# Sheet1.net
KiCad netlist of a schematic drawn in Altium Designer
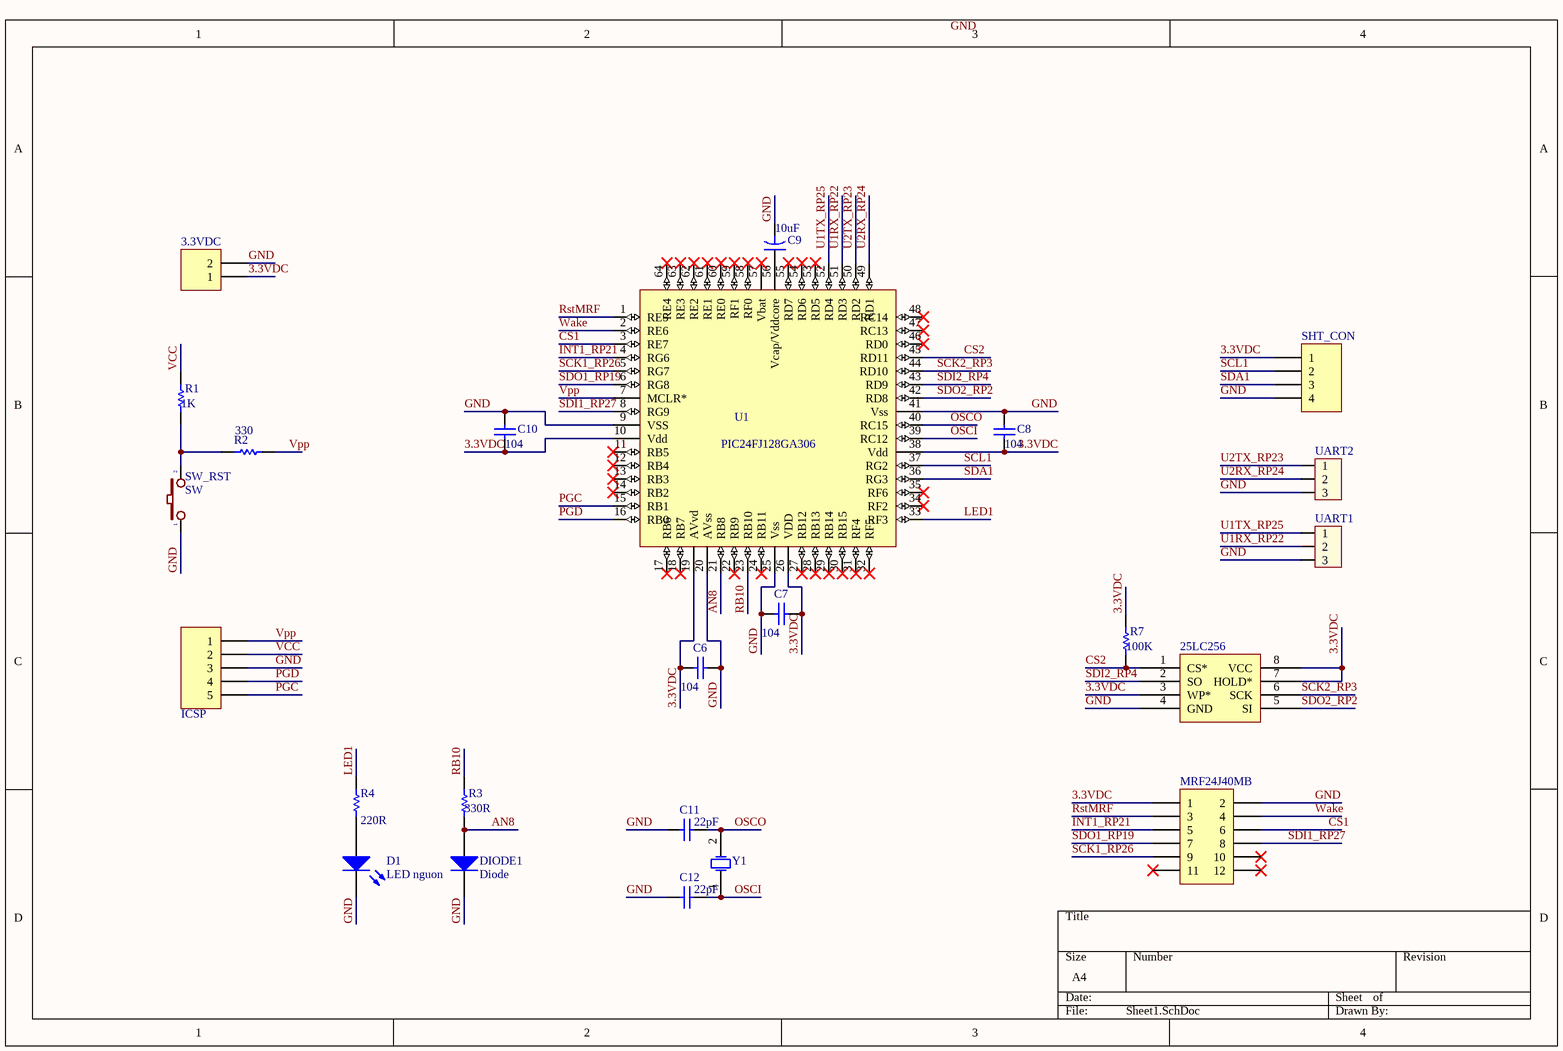
[diagram p0: Sheet1.SchDoc]

(export (version "E")
  (design (tool "Eeschema 10.0.6"))
  (components
    (comp (ref "3.3VDC")
      (value "OUT 3.3V")
      (footprint "HDR1X2")
      (description "Header, 2-Pin")
      (fields (field (name "PUBLISHER") "Altium Limited"))
      (libsource (lib "Miscellaneous Connectors") (part "Header 2"))
    )
    (comp (ref "25LC256") (value "25LC256") (footprint "DIP-8") (libsource (lib "25LC256") (part "25LC256")))
    (comp (ref "C6")
      (value "104")
      (footprint "C0805")
      (description "Capacitor")
      (fields (field (name "Comment") "Cap") (field (name "PUBLISHER") "Altium Limited"))
      (libsource (lib "Miscellaneous Devices") (part "Cap"))
    )
    (comp (ref "C7")
      (value "104")
      (footprint "C0805")
      (description "Capacitor")
      (fields (field (name "Comment") "Cap") (field (name "PUBLISHER") "Altium Limited"))
      (libsource (lib "Miscellaneous Devices") (part "Cap"))
    )
    (comp (ref "C8")
      (value "104")
      (footprint "C0805")
      (description "Capacitor")
      (fields (field (name "Comment") "Cap") (field (name "PUBLISHER") "Altium Limited"))
      (libsource (lib "Miscellaneous Devices") (part "Cap"))
    )
    (comp (ref "C9")
      (value "10uF")
      (footprint "CAP P 6.3x5.4")
      (description "Capacitor")
      (fields (field (name "Comment") "Cap2") (field (name "PUBLISHER") "Altium Limited"))
      (libsource (lib "Miscellaneous Devices") (part "Cap2"))
    )
    (comp (ref "C10")
      (value "104")
      (footprint "C0805")
      (description "Capacitor")
      (fields (field (name "Comment") "Cap") (field (name "PUBLISHER") "Altium Limited"))
      (libsource (lib "Miscellaneous Devices") (part "Cap"))
    )
    (comp (ref "C11")
      (value "22pF")
      (footprint "C0805")
      (description "Capacitor")
      (fields (field (name "Comment") "Cap") (field (name "PUBLISHER") "Altium Limited"))
      (libsource (lib "Miscellaneous Devices") (part "Cap"))
    )
    (comp (ref "C12")
      (value "22pF")
      (footprint "C0805")
      (description "Capacitor")
      (fields (field (name "Comment") "Cap") (field (name "PUBLISHER") "Altium Limited"))
      (libsource (lib "Miscellaneous Devices") (part "Cap"))
    )
    (comp (ref "D1")
      (value "LED nguon")
      (footprint "LED3mm")
      (description "Typical INFRARED GaAs LED")
      (fields (field (name "PUBLISHER") "Altium Limited"))
      (libsource (lib "Miscellaneous Devices") (part "LED0"))
    )
    (comp (ref "DIODE1")
      (value "Diode")
      (footprint "DZ0.5A")
      (description "Default Diode")
      (fields (field (name "PUBLISHER") "Altium Limited"))
      (libsource (lib "Miscellaneous Devices") (part "Diode"))
    )
    (comp (ref "ICSP")
      (value "ICSP")
      (footprint "CON5")
      (description "Header, 5-Pin")
      (fields (field (name "PUBLISHER") "Altium Limited"))
      (libsource (lib "Miscellaneous Connectors") (part "Header 5"))
    )
    (comp (ref "MRF24J40MB")
      (value "Header 6X2")
      (footprint "MRF24J40MB_board_mini")
      (description "Header, 6-Pin, Dual row")
      (fields (field (name "PUBLISHER") "Altium Limited"))
      (libsource (lib "Miscellaneous Connectors") (part "Header 6X2"))
    )
    (comp (ref "R1")
      (value "1K")
      (footprint "C0805")
      (description "Resistor")
      (fields (field (name "Comment") "Res1") (field (name "PUBLISHER") "Altium Limited"))
      (libsource (lib "Miscellaneous Devices") (part "Res1"))
    )
    (comp (ref "R2")
      (value "330")
      (footprint "C0805")
      (description "Resistor")
      (fields (field (name "Comment") "res") (field (name "PUBLISHER") "Altium Limited"))
      (libsource (lib "Miscellaneous Devices") (part "Res1"))
    )
    (comp (ref "R3")
      (value "330R")
      (footprint "C0805")
      (description "Resistor")
      (fields (field (name "Comment") "Res1") (field (name "PUBLISHER") "Altium Limited"))
      (libsource (lib "Miscellaneous Devices") (part "Res1"))
    )
    (comp (ref "R4")
      (value "220R")
      (footprint "C0805")
      (description "Resistor")
      (fields (field (name "Comment") "Res1") (field (name "PUBLISHER") "Altium Limited"))
      (libsource (lib "Miscellaneous Devices") (part "Res1"))
    )
    (comp (ref "R7")
      (value "100K")
      (footprint "C0805")
      (description "Semiconductor Resistor")
      (fields (field (name "Comment") "Res Semi") (field (name "PUBLISHER") "Altium Limited"))
      (libsource (lib "Miscellaneous Devices") (part "Res Semi"))
    )
    (comp (ref "SHT_CON")
      (value "SHT10 conector")
      (footprint "CON4")
      (description "Header, 4-Pin")
      (fields (field (name "PUBLISHER") "Altium Limited"))
      (libsource (lib "Miscellaneous Connectors") (part "Header 4"))
    )
    (comp (ref "SW_RST")
      (value "SW")
      (footprint "SW2")
      (description "Switch button 2 pin")
      (libsource (lib "syhaunguyen") (part "SW2"))
    )
    (comp (ref "U1")
      (value "PIC24FJ128GA306")
      (footprint "TQFP-PT64_N")
      (libsource (lib "Mylibbrary") (part "PIC24FJ128GA306"))
    )
    (comp (ref "UART1")
      (value "UART1")
      (footprint "CON3")
      (description "Connector 3")
      (libsource (lib "syhaunguyen") (part "Con3"))
    )
    (comp (ref "UART2")
      (value "UART2")
      (footprint "CON3")
      (description "Connector 3")
      (libsource (lib "syhaunguyen") (part "Con3"))
    )
    (comp (ref "Y1")
      (value "XTAL")
      (footprint "XT2")
      (description "Crystal Oscillator")
      (fields (field (name "PUBLISHER") "Altium Limited"))
      (libsource (lib "Miscellaneous Devices") (part "XTAL"))
    )
  )
  (nets
    (net (code "1") (name "/3.3VDC") (class "Default")
      (node (ref "25LC256") (pin "3") (pinfunction "WP*_3") (pintype "passive"))
      (node (ref "25LC256") (pin "7") (pinfunction "HOLD*_7") (pintype "passive"))
      (node (ref "25LC256") (pin "8") (pinfunction "VCC_8") (pintype "power_in"))
      (node (ref "3.3VDC") (pin "1") (pinfunction "1_1") (pintype "passive"))
      (node (ref "C10") (pin "1") (pinfunction "1_1") (pintype "passive"))
      (node (ref "C6") (pin "1") (pinfunction "1_1") (pintype "passive"))
      (node (ref "C7") (pin "2") (pinfunction "2_2") (pintype "passive"))
      (node (ref "C8") (pin "1") (pinfunction "1_1") (pintype "passive"))
      (node (ref "MRF24J40MB") (pin "1") (pinfunction "1_1") (pintype "passive"))
      (node (ref "R7") (pin "2") (pinfunction "2_2") (pintype "passive"))
      (node (ref "SHT_CON") (pin "1") (pinfunction "1_1") (pintype "passive"))
      (node (ref "U1") (pin "10") (pinfunction "Vdd_10") (pintype "passive"))
      (node (ref "U1") (pin "19") (pinfunction "AVvd_19") (pintype "power_in"))
      (node (ref "U1") (pin "26") (pinfunction "VDD_26") (pintype "power_in"))
      (node (ref "U1") (pin "38") (pinfunction "Vdd_38") (pintype "power_in"))
    )
    (net (code "2") (name "/AN8") (class "Default")
      (node (ref "DIODE1") (pin "1") (pinfunction "A_1") (pintype "passive"))
      (node (ref "R3") (pin "1") (pinfunction "1_1") (pintype "passive"))
      (node (ref "U1") (pin "21") (pinfunction "RB8_21") (pintype "bidirectional"))
    )
    (net (code "3") (name "/CS1") (class "Default")
      (node (ref "MRF24J40MB") (pin "6") (pinfunction "6_6") (pintype "passive"))
      (node (ref "U1") (pin "3") (pinfunction "RE7_3") (pintype "bidirectional"))
    )
    (net (code "4") (name "/CS2") (class "Default")
      (node (ref "25LC256") (pin "1") (pinfunction "CS*_1") (pintype "passive"))
      (node (ref "R7") (pin "1") (pinfunction "1_1") (pintype "passive"))
      (node (ref "U1") (pin "45") (pinfunction "RD11_45") (pintype "bidirectional"))
    )
    (net (code "5") (name "/GND") (class "Default")
      (node (ref "25LC256") (pin "4") (pinfunction "GND_4") (pintype "power_in"))
      (node (ref "3.3VDC") (pin "2") (pinfunction "2_2") (pintype "passive"))
      (node (ref "C10") (pin "2") (pinfunction "2_2") (pintype "passive"))
      (node (ref "C11") (pin "1") (pinfunction "1_1") (pintype "passive"))
      (node (ref "C12") (pin "1") (pinfunction "1_1") (pintype "passive"))
      (node (ref "C6") (pin "2") (pinfunction "2_2") (pintype "passive"))
      (node (ref "C7") (pin "1") (pinfunction "1_1") (pintype "passive"))
      (node (ref "C8") (pin "2") (pinfunction "2_2") (pintype "passive"))
      (node (ref "C9") (pin "2") (pinfunction "2_2") (pintype "passive"))
      (node (ref "D1") (pin "2") (pinfunction "K_2") (pintype "passive"))
      (node (ref "DIODE1") (pin "2") (pinfunction "K_2") (pintype "passive"))
      (node (ref "ICSP") (pin "3") (pinfunction "3_3") (pintype "passive"))
      (node (ref "MRF24J40MB") (pin "2") (pinfunction "2_2") (pintype "passive"))
      (node (ref "SHT_CON") (pin "4") (pinfunction "4_4") (pintype "passive"))
      (node (ref "SW_RST") (pin "1") (pinfunction "1_1") (pintype "passive"))
      (node (ref "U1") (pin "20") (pinfunction "AVss_20") (pintype "power_in"))
      (node (ref "U1") (pin "25") (pinfunction "Vss_25") (pintype "power_in"))
      (node (ref "U1") (pin "41") (pinfunction "Vss_41") (pintype "power_in"))
      (node (ref "U1") (pin "9") (pinfunction "VSS_9") (pintype "power_in"))
      (node (ref "UART1") (pin "3") (pinfunction "3_3") (pintype "passive"))
      (node (ref "UART2") (pin "3") (pinfunction "3_3") (pintype "passive"))
    )
    (net (code "6") (name "/INT1_RP21") (class "Default")
      (node (ref "MRF24J40MB") (pin "5") (pinfunction "5_5") (pintype "passive"))
      (node (ref "U1") (pin "4") (pinfunction "RG6_4") (pintype "bidirectional"))
    )
    (net (code "7") (name "/LED1") (class "Default")
      (node (ref "R4") (pin "2") (pinfunction "2_2") (pintype "passive"))
      (node (ref "U1") (pin "33") (pinfunction "RF3_33") (pintype "bidirectional"))
    )
    (net (code "8") (name "/OSCI") (class "Default")
      (node (ref "C12") (pin "2") (pinfunction "2_2") (pintype "passive"))
      (node (ref "U1") (pin "39") (pinfunction "RC12_39") (pintype "bidirectional"))
      (node (ref "Y1") (pin "1") (pinfunction "OSC1_1") (pintype "passive"))
    )
    (net (code "9") (name "/OSCO") (class "Default")
      (node (ref "C11") (pin "2") (pinfunction "2_2") (pintype "passive"))
      (node (ref "U1") (pin "40") (pinfunction "RC15_40") (pintype "bidirectional"))
      (node (ref "Y1") (pin "2") (pinfunction "OSC2_2") (pintype "passive"))
    )
    (net (code "10") (name "/PGC") (class "Default")
      (node (ref "ICSP") (pin "5") (pinfunction "5_5") (pintype "passive"))
      (node (ref "U1") (pin "15") (pinfunction "RB1_15") (pintype "bidirectional"))
    )
    (net (code "11") (name "/PGD") (class "Default")
      (node (ref "ICSP") (pin "4") (pinfunction "4_4") (pintype "passive"))
      (node (ref "U1") (pin "16") (pinfunction "RB0_16") (pintype "bidirectional"))
    )
    (net (code "12") (name "/RB10") (class "Default")
      (node (ref "R3") (pin "2") (pinfunction "2_2") (pintype "passive"))
      (node (ref "U1") (pin "23") (pinfunction "RB10_23") (pintype "bidirectional"))
    )
    (net (code "13") (name "/RstMRF") (class "Default")
      (node (ref "MRF24J40MB") (pin "3") (pinfunction "3_3") (pintype "passive"))
      (node (ref "U1") (pin "1") (pinfunction "RE5_1") (pintype "bidirectional"))
    )
    (net (code "14") (name "/SCK1_RP26") (class "Default")
      (node (ref "MRF24J40MB") (pin "9") (pinfunction "9_9") (pintype "passive"))
      (node (ref "U1") (pin "5") (pinfunction "RG7_5") (pintype "bidirectional"))
    )
    (net (code "15") (name "/SCK2_RP3") (class "Default")
      (node (ref "25LC256") (pin "6") (pinfunction "SCK_6") (pintype "passive"))
      (node (ref "U1") (pin "44") (pinfunction "RD10_44") (pintype "bidirectional"))
    )
    (net (code "16") (name "/SCL1") (class "Default")
      (node (ref "SHT_CON") (pin "2") (pinfunction "2_2") (pintype "passive"))
      (node (ref "U1") (pin "37") (pinfunction "RG2_37") (pintype "bidirectional"))
    )
    (net (code "17") (name "/SDA1") (class "Default")
      (node (ref "SHT_CON") (pin "3") (pinfunction "3_3") (pintype "passive"))
      (node (ref "U1") (pin "36") (pinfunction "RG3_36") (pintype "bidirectional"))
    )
    (net (code "18") (name "/SDI1_RP27") (class "Default")
      (node (ref "MRF24J40MB") (pin "8") (pinfunction "8_8") (pintype "passive"))
      (node (ref "U1") (pin "8") (pinfunction "RG9_8") (pintype "bidirectional"))
    )
    (net (code "19") (name "/SDI2_RP4") (class "Default")
      (node (ref "25LC256") (pin "2") (pinfunction "SO_2") (pintype "passive"))
      (node (ref "U1") (pin "43") (pinfunction "RD9_43") (pintype "bidirectional"))
    )
    (net (code "20") (name "/SDO1_RP19") (class "Default")
      (node (ref "MRF24J40MB") (pin "7") (pinfunction "7_7") (pintype "passive"))
      (node (ref "U1") (pin "6") (pinfunction "RG8_6") (pintype "bidirectional"))
    )
    (net (code "21") (name "/SDO2_RP2") (class "Default")
      (node (ref "25LC256") (pin "5") (pinfunction "SI_5") (pintype "passive"))
      (node (ref "U1") (pin "42") (pinfunction "RD8_42") (pintype "bidirectional"))
    )
    (net (code "22") (name "/U1RX_RP22") (class "Default")
      (node (ref "U1") (pin "51") (pinfunction "RD3_51") (pintype "bidirectional"))
      (node (ref "UART1") (pin "2") (pinfunction "2_2") (pintype "passive"))
    )
    (net (code "23") (name "/U1TX_RP25") (class "Default")
      (node (ref "U1") (pin "52") (pinfunction "RD4_52") (pintype "bidirectional"))
      (node (ref "UART1") (pin "1") (pinfunction "1_1") (pintype "passive"))
    )
    (net (code "24") (name "/U2RX_RP24") (class "Default")
      (node (ref "U1") (pin "49") (pinfunction "RD1_49") (pintype "bidirectional"))
      (node (ref "UART2") (pin "2") (pinfunction "2_2") (pintype "passive"))
    )
    (net (code "25") (name "/U2TX_RP23") (class "Default")
      (node (ref "U1") (pin "50") (pinfunction "RD2_50") (pintype "bidirectional"))
      (node (ref "UART2") (pin "1") (pinfunction "1_1") (pintype "passive"))
    )
    (net (code "26") (name "/VCC") (class "Default")
      (node (ref "ICSP") (pin "2") (pinfunction "2_2") (pintype "passive"))
      (node (ref "R1") (pin "2") (pinfunction "2_2") (pintype "passive"))
    )
    (net (code "27") (name "/Vpp") (class "Default")
      (node (ref "ICSP") (pin "1") (pinfunction "1_1") (pintype "passive"))
      (node (ref "R2") (pin "2") (pinfunction "2_2") (pintype "passive"))
      (node (ref "U1") (pin "7") (pinfunction "MCLR*_7") (pintype "passive"))
    )
    (net (code "28") (name "/Wake") (class "Default")
      (node (ref "MRF24J40MB") (pin "4") (pinfunction "4_4") (pintype "passive"))
      (node (ref "U1") (pin "2") (pinfunction "RE6_2") (pintype "bidirectional"))
    )
    (net (code "29") (name "Net-(D1-A)") (class "Default")
      (node (ref "D1") (pin "1") (pinfunction "A_1") (pintype "passive"))
      (node (ref "R4") (pin "1") (pinfunction "1_1") (pintype "passive"))
    )
    (net (code "30") (name "Net-(R1-Pad1)") (class "Default")
      (node (ref "R1") (pin "1") (pinfunction "1_1") (pintype "passive"))
      (node (ref "R2") (pin "1") (pinfunction "1_1") (pintype "passive"))
      (node (ref "SW_RST") (pin "2") (pinfunction "2_2") (pintype "passive"))
    )
    (net (code "31") (name "Net-(U1-Vcap{slash}Vddcore)") (class "Default")
      (node (ref "C9") (pin "1") (pinfunction "1_1") (pintype "passive"))
      (node (ref "U1") (pin "56") (pinfunction "Vcap/Vddcore_56") (pintype "power_in"))
    )
    (net (code "32") (name "unconnected-(MRF24J40MB-Pad10)") (class "Default")
      (node (ref "MRF24J40MB") (pin "10") (pinfunction "10_10") (pintype "passive+no_connect"))
    )
    (net (code "33") (name "unconnected-(MRF24J40MB-Pad11)") (class "Default")
      (node (ref "MRF24J40MB") (pin "11") (pinfunction "11_11") (pintype "passive+no_connect"))
    )
    (net (code "34") (name "unconnected-(MRF24J40MB-Pad12)") (class "Default")
      (node (ref "MRF24J40MB") (pin "12") (pinfunction "12_12") (pintype "passive+no_connect"))
    )
    (net (code "35") (name "unconnected-(U1-RB2-Pad14)") (class "Default")
      (node (ref "U1") (pin "14") (pinfunction "RB2_14") (pintype "bidirectional+no_connect"))
    )
    (net (code "36") (name "unconnected-(U1-RB3-Pad13)") (class "Default")
      (node (ref "U1") (pin "13") (pinfunction "RB3_13") (pintype "bidirectional+no_connect"))
    )
    (net (code "37") (name "unconnected-(U1-RB4-Pad12)") (class "Default")
      (node (ref "U1") (pin "12") (pinfunction "RB4_12") (pintype "bidirectional+no_connect"))
    )
    (net (code "38") (name "unconnected-(U1-RB5-Pad11)") (class "Default")
      (node (ref "U1") (pin "11") (pinfunction "RB5_11") (pintype "bidirectional+no_connect"))
    )
    (net (code "39") (name "unconnected-(U1-RB6-Pad17)") (class "Default")
      (node (ref "U1") (pin "17") (pinfunction "RB6_17") (pintype "bidirectional+no_connect"))
    )
    (net (code "40") (name "unconnected-(U1-RB7-Pad18)") (class "Default")
      (node (ref "U1") (pin "18") (pinfunction "RB7_18") (pintype "bidirectional+no_connect"))
    )
    (net (code "41") (name "unconnected-(U1-RB9-Pad22)") (class "Default")
      (node (ref "U1") (pin "22") (pinfunction "RB9_22") (pintype "bidirectional+no_connect"))
    )
    (net (code "42") (name "unconnected-(U1-RB11-Pad24)") (class "Default")
      (node (ref "U1") (pin "24") (pinfunction "RB11_24") (pintype "bidirectional+no_connect"))
    )
    (net (code "43") (name "unconnected-(U1-RB12-Pad27)") (class "Default")
      (node (ref "U1") (pin "27") (pinfunction "RB12_27") (pintype "bidirectional+no_connect"))
    )
    (net (code "44") (name "unconnected-(U1-RB13-Pad28)") (class "Default")
      (node (ref "U1") (pin "28") (pinfunction "RB13_28") (pintype "bidirectional+no_connect"))
    )
    (net (code "45") (name "unconnected-(U1-RB14-Pad29)") (class "Default")
      (node (ref "U1") (pin "29") (pinfunction "RB14_29") (pintype "bidirectional+no_connect"))
    )
    (net (code "46") (name "unconnected-(U1-RB15-Pad30)") (class "Default")
      (node (ref "U1") (pin "30") (pinfunction "RB15_30") (pintype "bidirectional+no_connect"))
    )
    (net (code "47") (name "unconnected-(U1-RC13-Pad47)") (class "Default")
      (node (ref "U1") (pin "47") (pinfunction "RC13_47") (pintype "bidirectional+no_connect"))
    )
    (net (code "48") (name "unconnected-(U1-RC14-Pad48)") (class "Default")
      (node (ref "U1") (pin "48") (pinfunction "RC14_48") (pintype "bidirectional+no_connect"))
    )
    (net (code "49") (name "unconnected-(U1-RD0-Pad46)") (class "Default")
      (node (ref "U1") (pin "46") (pinfunction "RD0_46") (pintype "bidirectional+no_connect"))
    )
    (net (code "50") (name "unconnected-(U1-RD5-Pad53)") (class "Default")
      (node (ref "U1") (pin "53") (pinfunction "RD5_53") (pintype "bidirectional+no_connect"))
    )
    (net (code "51") (name "unconnected-(U1-RD6-Pad54)") (class "Default")
      (node (ref "U1") (pin "54") (pinfunction "RD6_54") (pintype "bidirectional+no_connect"))
    )
    (net (code "52") (name "unconnected-(U1-RD7-Pad55)") (class "Default")
      (node (ref "U1") (pin "55") (pinfunction "RD7_55") (pintype "bidirectional+no_connect"))
    )
    (net (code "53") (name "unconnected-(U1-RE0-Pad60)") (class "Default")
      (node (ref "U1") (pin "60") (pinfunction "RE0_60") (pintype "bidirectional+no_connect"))
    )
    (net (code "54") (name "unconnected-(U1-RE1-Pad61)") (class "Default")
      (node (ref "U1") (pin "61") (pinfunction "RE1_61") (pintype "bidirectional+no_connect"))
    )
    (net (code "55") (name "unconnected-(U1-RE2-Pad62)") (class "Default")
      (node (ref "U1") (pin "62") (pinfunction "RE2_62") (pintype "bidirectional+no_connect"))
    )
    (net (code "56") (name "unconnected-(U1-RE3-Pad63)") (class "Default")
      (node (ref "U1") (pin "63") (pinfunction "RE3_63") (pintype "bidirectional+no_connect"))
    )
    (net (code "57") (name "unconnected-(U1-RE4-Pad64)") (class "Default")
      (node (ref "U1") (pin "64") (pinfunction "RE4_64") (pintype "bidirectional+no_connect"))
    )
    (net (code "58") (name "unconnected-(U1-RF0-Pad58)") (class "Default")
      (node (ref "U1") (pin "58") (pinfunction "RF0_58") (pintype "bidirectional+no_connect"))
    )
    (net (code "59") (name "unconnected-(U1-RF1-Pad59)") (class "Default")
      (node (ref "U1") (pin "59") (pinfunction "RF1_59") (pintype "bidirectional+no_connect"))
    )
    (net (code "60") (name "unconnected-(U1-RF2-Pad34)") (class "Default")
      (node (ref "U1") (pin "34") (pinfunction "RF2_34") (pintype "bidirectional+no_connect"))
    )
    (net (code "61") (name "unconnected-(U1-RF4-Pad31)") (class "Default")
      (node (ref "U1") (pin "31") (pinfunction "RF4_31") (pintype "bidirectional+no_connect"))
    )
    (net (code "62") (name "unconnected-(U1-RF5-Pad32)") (class "Default")
      (node (ref "U1") (pin "32") (pinfunction "RF5_32") (pintype "bidirectional+no_connect"))
    )
    (net (code "63") (name "unconnected-(U1-RF6-Pad35)") (class "Default")
      (node (ref "U1") (pin "35") (pinfunction "RF6_35") (pintype "bidirectional+no_connect"))
    )
    (net (code "64") (name "unconnected-(U1-Vbat-Pad57)") (class "Default")
      (node (ref "U1") (pin "57") (pinfunction "Vbat_57") (pintype "power_in+no_connect"))
    )
  )
)
